# GSM_Stat_LED_Driver.net
KiCad netlist of a schematic drawn in Altium Designer
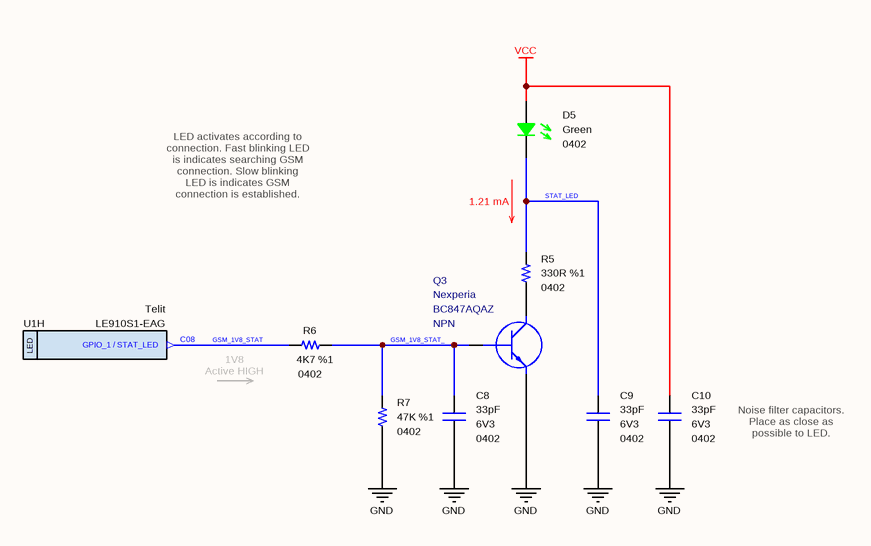
[diagram p0: GSM Stat LED Driver.SchDoc]

(export (version "E")
  (design (tool "Eeschema 10.0.6"))
  (components
    (comp (ref "C8")
      (value "33pF")
      (footprint "CAPACITOR_0402")
      (description "Capacitor - 33pF [0402] (Ceramic)")
      (fields
        (field (name "CASE") "0402")
        (field (name "VOLTAGE") "6V3")
        (field (name "MANUFACTURER PART NUMBER") "C0402C330J9RACAUTO")
        (field (name "TOLERANCE") "10%")
      )
      (libsource (lib "P101DA_Library") (part "33pF [0402-6V3]"))
    )
    (comp (ref "C9")
      (value "33pF")
      (footprint "CAPACITOR_0402")
      (description "Capacitor - 33pF [0402] (Ceramic)")
      (fields
        (field (name "CASE") "0402")
        (field (name "VOLTAGE") "6V3")
        (field (name "MANUFACTURER PART NUMBER") "C0402C330J9RACAUTO")
        (field (name "TOLERANCE") "10%")
      )
      (libsource (lib "P101DA_Library") (part "33pF [0402-6V3]"))
    )
    (comp (ref "C10")
      (value "33pF")
      (footprint "CAPACITOR_0402")
      (description "Capacitor - 33pF [0402] (Ceramic)")
      (fields
        (field (name "CASE") "0402")
        (field (name "VOLTAGE") "6V3")
        (field (name "MANUFACTURER PART NUMBER") "C0402C330J9RACAUTO")
        (field (name "TOLERANCE") "10%")
      )
      (libsource (lib "P101DA_Library") (part "33pF [0402-6V3]"))
    )
    (comp (ref "D5")
      (value "~")
      (footprint "LED_0402")
      (description "Standard LEDs - SMD MINI-MOLD ULTRA COMPACT GREEN")
      (fields
        (field (name "MANUFACTURER PART NUMBER") "SML-P12MTT86R")
        (field (name "CASE") "0402")
        (field (name "COLOR") "Green")
      )
      (libsource (lib "P101DA_Library") (part "LED (0402-Green)"))
    )
    (comp (ref "Q3")
      (value "~")
      (footprint "SOT1215")
      (description "Bipolar NPN Transistors")
      (fields
        (field (name "POLARITY") "NPN")
        (field (name "MANUFACTURER PART NUMBER") "BC847AQAZ")
        (field (name "MANUFACTURER NAME") "Nexperia")
      )
      (libsource (lib "P101DA_Library") (part "BC847"))
    )
    (comp (ref "R5")
      (value "330R")
      (footprint "RESISTOR_0402")
      (description "Thick Film Resistors - SMD 1/16 W 330 Ohm 1%")
      (fields
        (field (name "CASE") "0402")
        (field (name "MANUFACTURER PART NUMBER") "CRCW0402330RFKED")
        (field (name "TOLERANCE") "%1")
      )
      (libsource (lib "P101DA_Library") (part "330R"))
    )
    (comp (ref "R6")
      (value "4K7")
      (footprint "RESISTOR_0402")
      (description "Thick Film Resistors - SMD 1/16 W 4.7 Kohms 1%")
      (fields
        (field (name "CASE") "0402")
        (field (name "MANUFACTURER PART NUMBER") "CRCW04024K70FKED")
        (field (name "TOLERANCE") "%1")
      )
      (libsource (lib "P101DA_Library") (part "4K7"))
    )
    (comp (ref "R7")
      (value "47K")
      (footprint "RESISTOR_0402")
      (description "Thick Film Resistors - SMD 1/16 W 47 Kohms 1%")
      (fields
        (field (name "CASE") "0402")
        (field (name "MANUFACTURER PART NUMBER") "CRCW040247K0FKED")
        (field (name "TOLERANCE") "%1")
      )
      (libsource (lib "P101DA_Library") (part "47K"))
    )
    (comp (ref "U1")
      (value "LE910S1-EAG LTE GSM Module")
      (footprint "LE910 GSM Modem")
      (description "Telit LE910S1-EAG GPRS/GNSS Module")
      (fields
        (field (name "MANUFACTURER PART NUMBER") "LE910S1-EAG")
        (field (name "MANUFACTURER NAME") "Telit")
      )
      (libsource (lib "P101DA_Library") (part "IC - LE910S1-EAG"))
    )
  )
  (nets
    (net (code "1") (name "/GSM_1V8_STAT") (class "Default")
      (node (ref "R6") (pin "2") (pinfunction "2_2") (pintype "passive"))
      (node (ref "U1") (pin "C08") (pinfunction "GPIO_1_/_STAT_LED_C08") (pintype "output"))
    )
    (net (code "2") (name "/GSM_1V8_STAT_") (class "Default")
      (node (ref "C8") (pin "2") (pinfunction "2_2") (pintype "passive"))
      (node (ref "Q3") (pin "1") (pinfunction "B_1") (pintype "passive"))
      (node (ref "R6") (pin "1") (pinfunction "1_1") (pintype "passive"))
      (node (ref "R7") (pin "2") (pinfunction "2_2") (pintype "passive"))
    )
    (net (code "3") (name "/STAT_LED") (class "Default")
      (node (ref "C9") (pin "2") (pinfunction "2_2") (pintype "passive"))
      (node (ref "D5") (pin "1") (pinfunction "1_1") (pintype "passive"))
      (node (ref "R5") (pin "2") (pinfunction "2_2") (pintype "passive"))
    )
    (net (code "4") (name "GND") (class "Default")
      (node (ref "C10") (pin "1") (pinfunction "1_1") (pintype "passive"))
      (node (ref "C8") (pin "1") (pinfunction "1_1") (pintype "passive"))
      (node (ref "C9") (pin "1") (pinfunction "1_1") (pintype "passive"))
      (node (ref "Q3") (pin "2") (pinfunction "E_2") (pintype "passive"))
      (node (ref "R7") (pin "1") (pinfunction "1_1") (pintype "passive"))
    )
    (net (code "5") (name "Net-(Q3-C)") (class "Default")
      (node (ref "Q3") (pin "3") (pinfunction "C_3") (pintype "passive"))
      (node (ref "R5") (pin "1") (pinfunction "1_1") (pintype "passive"))
    )
    (net (code "6") (name "VCC") (class "Default")
      (node (ref "C10") (pin "2") (pinfunction "2_2") (pintype "passive"))
      (node (ref "D5") (pin "2") (pinfunction "2_2") (pintype "passive"))
    )
  )
)
